# CW308T-FE310-G002-CONN.net
KiCad netlist of a schematic drawn in Altium Designer
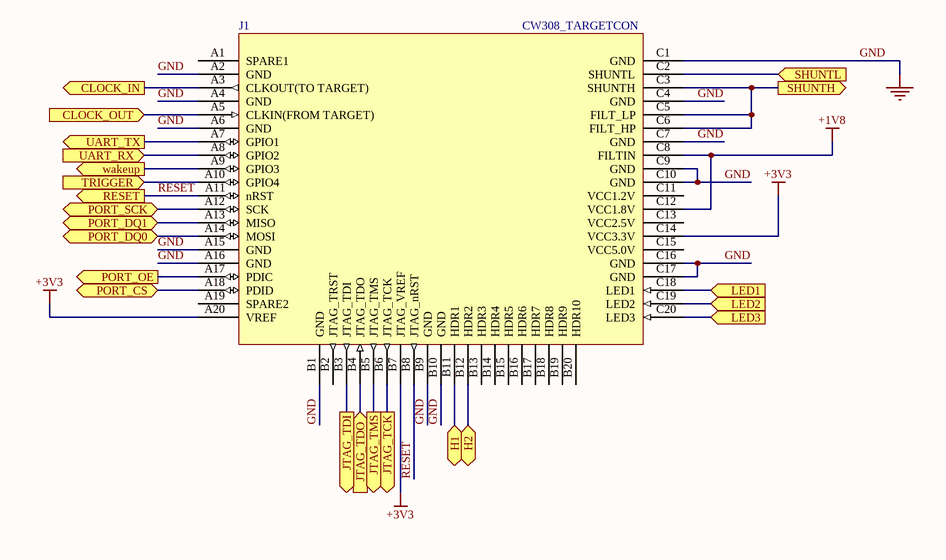
[diagram p0: CW308T-FE310-G002-CONN.SchDoc]

(export (version "E")
  (design (tool "Eeschema 10.0.6"))
  (components
    (comp (ref "J1")
      (value "CW308_TARGETCON")
      (footprint "CW308_TBOARD_CONN")
      (description "CW308 \"Standard\" Target Board Connector")
      (fields (field (name "PART NUMBER") "CW308_TBOARD"))
      (libsource (lib "NewAE_AltiumLib") (part "CW308_TBOARD"))
    )
  )
  (nets
    (net (code "1") (name "+1V8") (class "Default")
      (node (ref "J1") (pin "C12") (pinfunction "VCC1.8V_C12") (pintype "power_in"))
      (node (ref "J1") (pin "C8") (pinfunction "FILTIN_C8") (pintype "passive"))
    )
    (net (code "2") (name "+3V3") (class "Default")
      (node (ref "J1") (pin "A20") (pinfunction "VREF_A20") (pintype "tri_state"))
      (node (ref "J1") (pin "B7") (pinfunction "JTAG_VREF_B7") (pintype "tri_state"))
      (node (ref "J1") (pin "C14") (pinfunction "VCC3.3V_C14") (pintype "power_in"))
    )
    (net (code "3") (name "/CLOCK_IN") (class "Default")
      (node (ref "J1") (pin "A3") (pinfunction "CLKOUT(TO_TARGET)_A3") (pintype "output"))
    )
    (net (code "4") (name "/CLOCK_OUT") (class "Default")
      (node (ref "J1") (pin "A5") (pinfunction "CLKIN(FROM_TARGET)_A5") (pintype "input"))
    )
    (net (code "5") (name "/H1") (class "Default")
      (node (ref "J1") (pin "B11") (pinfunction "HDR1_B11") (pintype "passive"))
    )
    (net (code "6") (name "/H2") (class "Default")
      (node (ref "J1") (pin "B12") (pinfunction "HDR2_B12") (pintype "passive"))
    )
    (net (code "7") (name "/JTAG_TCK") (class "Default")
      (node (ref "J1") (pin "B6") (pinfunction "JTAG_TCK_B6") (pintype "output"))
    )
    (net (code "8") (name "/JTAG_TDI") (class "Default")
      (node (ref "J1") (pin "B3") (pinfunction "JTAG_TDI_B3") (pintype "output"))
    )
    (net (code "9") (name "/JTAG_TDO") (class "Default")
      (node (ref "J1") (pin "B4") (pinfunction "JTAG_TDO_B4") (pintype "input"))
    )
    (net (code "10") (name "/JTAG_TMS") (class "Default")
      (node (ref "J1") (pin "B5") (pinfunction "JTAG_TMS_B5") (pintype "output"))
    )
    (net (code "11") (name "/LED1") (class "Default")
      (node (ref "J1") (pin "C18") (pinfunction "LED1_C18") (pintype "input"))
    )
    (net (code "12") (name "/LED2") (class "Default")
      (node (ref "J1") (pin "C19") (pinfunction "LED2_C19") (pintype "input"))
    )
    (net (code "13") (name "/LED3") (class "Default")
      (node (ref "J1") (pin "C20") (pinfunction "LED3_C20") (pintype "input"))
    )
    (net (code "14") (name "/PORT_CS") (class "Default")
      (node (ref "J1") (pin "A18") (pinfunction "PDID_A18") (pintype "bidirectional"))
    )
    (net (code "15") (name "/PORT_DQ0") (class "Default")
      (node (ref "J1") (pin "A14") (pinfunction "MOSI_A14") (pintype "bidirectional"))
    )
    (net (code "16") (name "/PORT_DQ1") (class "Default")
      (node (ref "J1") (pin "A13") (pinfunction "MISO_A13") (pintype "bidirectional"))
    )
    (net (code "17") (name "/PORT_OE") (class "Default")
      (node (ref "J1") (pin "A17") (pinfunction "PDIC_A17") (pintype "bidirectional"))
    )
    (net (code "18") (name "/PORT_SCK") (class "Default")
      (node (ref "J1") (pin "A12") (pinfunction "SCK_A12") (pintype "bidirectional"))
    )
    (net (code "19") (name "/RESET") (class "Default")
      (node (ref "J1") (pin "A11") (pinfunction "nRST_A11") (pintype "bidirectional"))
      (node (ref "J1") (pin "B8") (pinfunction "JTAG_nRST_B8") (pintype "output"))
    )
    (net (code "20") (name "/SHUNTH") (class "Default")
      (node (ref "J1") (pin "C3") (pinfunction "SHUNTH_C3") (pintype "passive"))
      (node (ref "J1") (pin "C5") (pinfunction "FILT_LP_C5") (pintype "passive"))
      (node (ref "J1") (pin "C6") (pinfunction "FILT_HP_C6") (pintype "passive"))
    )
    (net (code "21") (name "/SHUNTL") (class "Default")
      (node (ref "J1") (pin "C2") (pinfunction "SHUNTL_C2") (pintype "passive"))
    )
    (net (code "22") (name "/TRIGGER") (class "Default")
      (node (ref "J1") (pin "A10") (pinfunction "GPIO4_A10") (pintype "bidirectional"))
    )
    (net (code "23") (name "/UART_RX") (class "Default")
      (node (ref "J1") (pin "A8") (pinfunction "GPIO2_A8") (pintype "bidirectional"))
    )
    (net (code "24") (name "/UART_TX") (class "Default")
      (node (ref "J1") (pin "A7") (pinfunction "GPIO1_A7") (pintype "bidirectional"))
    )
    (net (code "25") (name "/wakeup") (class "Default")
      (node (ref "J1") (pin "A9") (pinfunction "GPIO3_A9") (pintype "bidirectional"))
    )
    (net (code "26") (name "GND") (class "Default")
      (node (ref "J1") (pin "A15") (pinfunction "GND_A15") (pintype "passive"))
      (node (ref "J1") (pin "A16") (pinfunction "GND_A16") (pintype "passive"))
      (node (ref "J1") (pin "A2") (pinfunction "GND_A2") (pintype "passive"))
      (node (ref "J1") (pin "A4") (pinfunction "GND_A4") (pintype "passive"))
      (node (ref "J1") (pin "A6") (pinfunction "GND_A6") (pintype "power_in"))
      (node (ref "J1") (pin "B1") (pinfunction "GND_B1") (pintype "passive"))
      (node (ref "J1") (pin "B10") (pinfunction "GND_B10") (pintype "passive"))
      (node (ref "J1") (pin "B9") (pinfunction "GND_B9") (pintype "passive"))
      (node (ref "J1") (pin "C1") (pinfunction "GND_C1") (pintype "power_in"))
      (node (ref "J1") (pin "C10") (pinfunction "GND_C10") (pintype "power_in"))
      (node (ref "J1") (pin "C16") (pinfunction "GND_C16") (pintype "power_in"))
      (node (ref "J1") (pin "C17") (pinfunction "GND_C17") (pintype "power_in"))
      (node (ref "J1") (pin "C4") (pinfunction "GND_C4") (pintype "power_in"))
      (node (ref "J1") (pin "C7") (pinfunction "GND_C7") (pintype "power_in"))
      (node (ref "J1") (pin "C9") (pinfunction "GND_C9") (pintype "power_in"))
    )
    (net (code "27") (name "unconnected-(J1-HDR3-PadB13)") (class "Default")
      (node (ref "J1") (pin "B13") (pinfunction "HDR3_B13") (pintype "passive"))
    )
    (net (code "28") (name "unconnected-(J1-HDR4-PadB14)") (class "Default")
      (node (ref "J1") (pin "B14") (pinfunction "HDR4_B14") (pintype "passive"))
    )
    (net (code "29") (name "unconnected-(J1-HDR5-PadB15)") (class "Default")
      (node (ref "J1") (pin "B15") (pinfunction "HDR5_B15") (pintype "passive"))
    )
    (net (code "30") (name "unconnected-(J1-HDR6-PadB16)") (class "Default")
      (node (ref "J1") (pin "B16") (pinfunction "HDR6_B16") (pintype "passive"))
    )
    (net (code "31") (name "unconnected-(J1-HDR7-PadB17)") (class "Default")
      (node (ref "J1") (pin "B17") (pinfunction "HDR7_B17") (pintype "passive"))
    )
    (net (code "32") (name "unconnected-(J1-HDR8-PadB18)") (class "Default")
      (node (ref "J1") (pin "B18") (pinfunction "HDR8_B18") (pintype "passive"))
    )
    (net (code "33") (name "unconnected-(J1-HDR9-PadB19)") (class "Default")
      (node (ref "J1") (pin "B19") (pinfunction "HDR9_B19") (pintype "passive"))
    )
    (net (code "34") (name "unconnected-(J1-HDR10-PadB20)") (class "Default")
      (node (ref "J1") (pin "B20") (pinfunction "HDR10_B20") (pintype "passive"))
    )
    (net (code "35") (name "unconnected-(J1-JTAG_TRST-PadB2)") (class "Default")
      (node (ref "J1") (pin "B2") (pinfunction "JTAG_TRST_B2") (pintype "output"))
    )
    (net (code "36") (name "unconnected-(J1-SPARE1-PadA1)") (class "Default")
      (node (ref "J1") (pin "A1") (pinfunction "SPARE1_A1") (pintype "passive"))
    )
    (net (code "37") (name "unconnected-(J1-SPARE2-PadA19)") (class "Default")
      (node (ref "J1") (pin "A19") (pinfunction "SPARE2_A19") (pintype "passive"))
    )
    (net (code "38") (name "unconnected-(J1-VCC1.2V-PadC11)") (class "Default")
      (node (ref "J1") (pin "C11") (pinfunction "VCC1.2V_C11") (pintype "power_in"))
    )
    (net (code "39") (name "unconnected-(J1-VCC2.5V-PadC13)") (class "Default")
      (node (ref "J1") (pin "C13") (pinfunction "VCC2.5V_C13") (pintype "power_in"))
    )
    (net (code "40") (name "unconnected-(J1-VCC5.0V-PadC15)") (class "Default")
      (node (ref "J1") (pin "C15") (pinfunction "VCC5.0V_C15") (pintype "power_in"))
    )
  )
)
